# 5_-MCU_CONNECTORS.net
KiCad netlist of a schematic drawn in Altium Designer
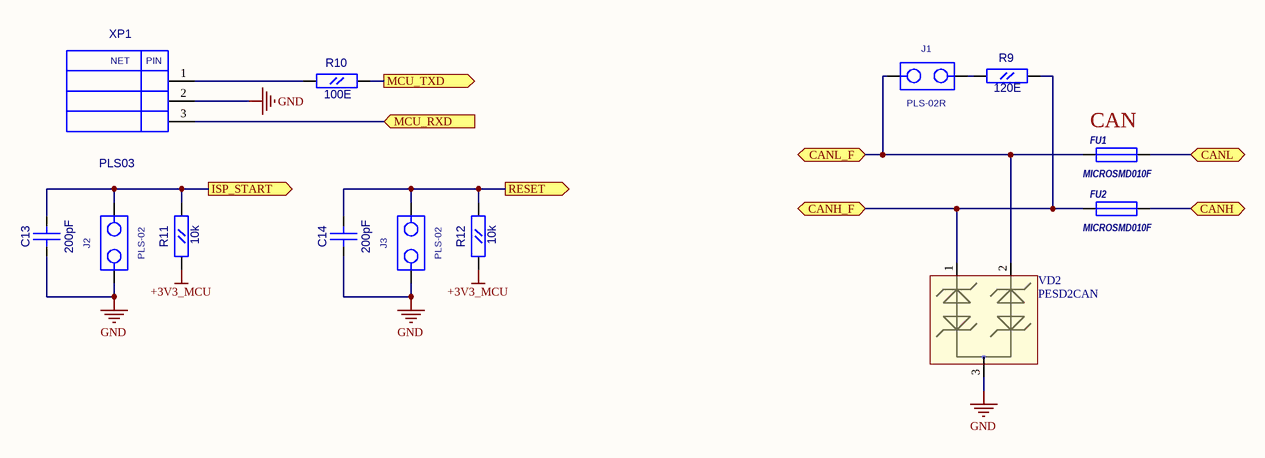
[diagram p0: [5]-MCU_CONNECTORS.SchDoc]

(export (version "E")
  (design (tool "Eeschema 10.0.6"))
  (components
    (comp (ref "C13")
      (value "200pF")
      (footprint "CC0603")
      (description "CC0603")
      (libsource (lib "gprs_modem_2") (part "CC0603"))
    )
    (comp (ref "C14")
      (value "200pF")
      (footprint "CC0603")
      (description "CC0603")
      (libsource (lib "gprs_modem_2") (part "CC0603"))
    )
    (comp (ref "FU1")
      (value "MICROSMD010F")
      (footprint "RC1210")
      (description "MICROSMD")
      (libsource (lib "gprs_modem_2") (part "MICROSMD"))
    )
    (comp (ref "FU2")
      (value "MICROSMD010F")
      (footprint "RC1210")
      (description "MICROSMD")
      (libsource (lib "gprs_modem_2") (part "MICROSMD"))
    )
    (comp (ref "J1")
      (value "PLS-02R")
      (footprint "PLS-02R")
      (libsource (lib "fizik_lib (1)") (part "PLS-02R"))
    )
    (comp (ref "J2") (value "PLS-02") (footprint "PLS-02") (libsource (lib "fizik_lib (1)") (part "PLS-02")))
    (comp (ref "J3") (value "PLS-02") (footprint "PLS-02") (libsource (lib "fizik_lib (1)") (part "PLS-02")))
    (comp (ref "R9")
      (value "120E")
      (footprint "RC0805")
      (description "RC0805")
      (libsource (lib "fizik_lib") (part "RC0805"))
    )
    (comp (ref "R10")
      (value "100E")
      (footprint "RC0603")
      (description "RC0603")
      (libsource (lib "gprs_modem_2") (part "RC0603"))
    )
    (comp (ref "R11")
      (value "10k")
      (footprint "RC0603")
      (description "RC0603")
      (libsource (lib "gprs_modem_2") (part "RC0603"))
    )
    (comp (ref "R12")
      (value "10k")
      (footprint "RC0603")
      (description "RC0603")
      (libsource (lib "gprs_modem_2") (part "RC0603"))
    )
    (comp (ref "VD2")
      (value "PESD2CAN")
      (footprint "SOT-23(123)")
      (description "TVS for CAN")
      (libsource (lib "gprs_modem_2") (part "PESD2CAN"))
    )
    (comp (ref "XP1") (value "PLS03") (footprint "PLS-03") (libsource (lib "fizik_lib (1)") (part "PLS03")))
  )
  (nets
    (net (code "1") (name "+3V3_MCU") (class "Default")
      (node (ref "R11") (pin "1") (pinfunction "A_1") (pintype "passive"))
      (node (ref "R12") (pin "1") (pinfunction "A_1") (pintype "passive"))
    )
    (net (code "2") (name "/CANH") (class "Default") (node (ref "FU2") (pin "2") (pintype "passive")))
    (net (code "3") (name "/CANH_F") (class "Default")
      (node (ref "FU2") (pin "1") (pintype "passive"))
      (node (ref "R9") (pin "2") (pinfunction "B_2") (pintype "passive"))
      (node (ref "VD2") (pin "1") (pinfunction "1_1") (pintype "passive"))
    )
    (net (code "4") (name "/CANL") (class "Default") (node (ref "FU1") (pin "2") (pintype "passive")))
    (net (code "5") (name "/CANL_F") (class "Default")
      (node (ref "FU1") (pin "1") (pintype "passive"))
      (node (ref "J1") (pin "1") (pintype "passive"))
      (node (ref "VD2") (pin "2") (pinfunction "2_2") (pintype "passive"))
    )
    (net (code "6") (name "/ISP_START") (class "Default")
      (node (ref "C13") (pin "2") (pinfunction "B_2") (pintype "passive"))
      (node (ref "J2") (pin "2") (pintype "passive"))
      (node (ref "R11") (pin "2") (pinfunction "B_2") (pintype "passive"))
    )
    (net (code "7") (name "/MCU_RXD") (class "Default")
      (node (ref "XP1") (pin "3") (pinfunction "3_3") (pintype "passive"))
    )
    (net (code "8") (name "/MCU_TXD") (class "Default")
      (node (ref "R10") (pin "2") (pinfunction "B_2") (pintype "passive"))
    )
    (net (code "9") (name "/RESET") (class "Default")
      (node (ref "C14") (pin "2") (pinfunction "B_2") (pintype "passive"))
      (node (ref "J3") (pin "2") (pintype "passive"))
      (node (ref "R12") (pin "2") (pinfunction "B_2") (pintype "passive"))
    )
    (net (code "10") (name "GND") (class "Default")
      (node (ref "C13") (pin "1") (pinfunction "A_1") (pintype "passive"))
      (node (ref "C14") (pin "1") (pinfunction "A_1") (pintype "passive"))
      (node (ref "J2") (pin "1") (pintype "passive"))
      (node (ref "J3") (pin "1") (pintype "passive"))
      (node (ref "VD2") (pin "3") (pinfunction "3_3") (pintype "passive"))
      (node (ref "XP1") (pin "2") (pinfunction "2_2") (pintype "passive"))
    )
    (net (code "11") (name "Net-(R9-A)") (class "Default")
      (node (ref "J1") (pin "2") (pintype "passive"))
      (node (ref "R9") (pin "1") (pinfunction "A_1") (pintype "passive"))
    )
    (net (code "12") (name "Net-(R10-A)") (class "Default")
      (node (ref "R10") (pin "1") (pinfunction "A_1") (pintype "passive"))
      (node (ref "XP1") (pin "1") (pinfunction "1_1") (pintype "passive"))
    )
  )
)
